# Sheet1.net
KiCad netlist of a schematic drawn in Altium Designer
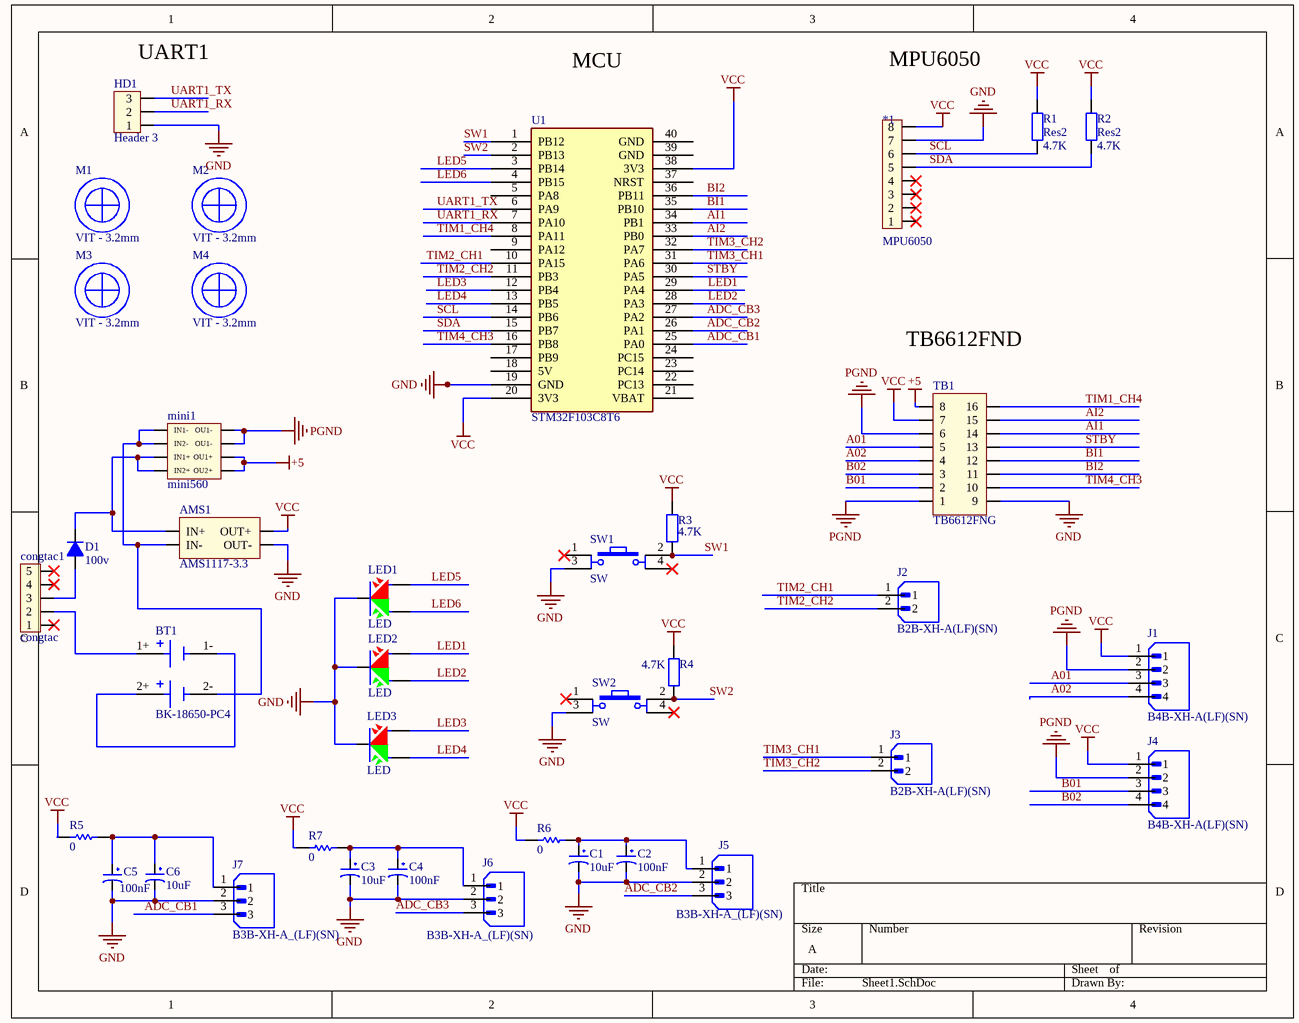
[diagram p0: Sheet1.SchDoc]

(export (version "E")
  (design (tool "Eeschema 10.0.6"))
  (components
    (comp (ref "*1") (value "MPU6050") (footprint "MPU6050") (libsource (lib "lpson") (part "MPU6050")))
    (comp (ref "AMS1")
      (value "AMS1117-3.3")
      (footprint "ASM1117-3.3")
      (libsource (lib "lpson") (part "AMS1117-3.3"))
    )
    (comp (ref "BT1")
      (value "BK-18650-PC4")
      (footprint "BAT_BK-18650-PC4")
      (description "Battery Holder (Open) 18650 2 Cell PC Pin")
      (libsource (lib "BK-18650-PC4") (part "BK-18650-PC4"))
    )
    (comp (ref "C1")
      (value "10uF")
      (footprint "CP1/2")
      (description "Cap P  0,1uF < 22uF , 16 - 50V")
      (libsource (lib "lpson") (part "CP1"))
    )
    (comp (ref "C2")
      (value "100nF")
      (footprint "CP1/2")
      (description "Cap P  0,1uF < 22uF , 16 - 50V")
      (libsource (lib "lpson") (part "CP1"))
    )
    (comp (ref "C3")
      (value "10uF")
      (footprint "CP1/2")
      (description "Cap P  0,1uF < 22uF , 16 - 50V")
      (libsource (lib "lpson") (part "CP1"))
    )
    (comp (ref "C4")
      (value "100nF")
      (footprint "CP1/2")
      (description "Cap P  0,1uF < 22uF , 16 - 50V")
      (libsource (lib "lpson") (part "CP1"))
    )
    (comp (ref "C5")
      (value "100nF")
      (footprint "CP1/2")
      (description "Cap P  0,1uF < 22uF , 16 - 50V")
      (libsource (lib "lpson") (part "CP1"))
    )
    (comp (ref "C6")
      (value "10uF")
      (footprint "CP1/2")
      (description "Cap P  0,1uF < 22uF , 16 - 50V")
      (libsource (lib "lpson") (part "CP1"))
    )
    (comp (ref "congtac1") (value "congtac") (footprint "congtac") (libsource (lib "lpson") (part "congtac")))
    (comp (ref "D1")
      (value "100v")
      (footprint "Diode 1N4007")
      (description "Cắm")
      (libsource (lib "THU VIEN SCH") (part "Diode 1N4148"))
    )
    (comp (ref "HD1") (value "Header 3") (footprint "Header_3") (libsource (lib "lpson") (part "Header3")))
    (comp (ref "J1")
      (value "B4B-XH-A(LF)(SN)")
      (footprint "JST_B4B-XH-A(LF)(SN)")
      (description "Connector Header Through Hole 4 position 0.098 (2.50mm)")
      (fields (field (name "MF") "JST Sales"))
      (libsource (lib "B4B-XH-A_LF__SN_") (part "B4B-XH-A(LF)(SN)"))
    )
    (comp (ref "J2")
      (value "B2B-XH-A(LF)(SN)")
      (footprint "JST_B2B-XH-A(LF)(SN)")
      (description "Connector Header Through Hole 2 position 0.098 (2.50mm)")
      (fields (field (name "MF") "JST Sales America Inc."))
      (libsource (lib "B2B-XH-A_LF__SN_") (part "B2B-XH-A(LF)(SN)"))
    )
    (comp (ref "J3")
      (value "B2B-XH-A(LF)(SN)")
      (footprint "JST_B2B-XH-A(LF)(SN)")
      (description "Connector Header Through Hole 2 position 0.098 (2.50mm)")
      (fields (field (name "MF") "JST Sales America Inc."))
      (libsource (lib "B2B-XH-A_LF__SN_") (part "B2B-XH-A(LF)(SN)"))
    )
    (comp (ref "J4")
      (value "B4B-XH-A(LF)(SN)")
      (footprint "JST_B4B-XH-A(LF)(SN)")
      (description "Connector Header Through Hole 4 position 0.098 (2.50mm)")
      (fields (field (name "MF") "JST Sales"))
      (libsource (lib "B4B-XH-A_LF__SN_") (part "B4B-XH-A(LF)(SN)"))
    )
    (comp (ref "J5")
      (value "B3B-XH-A_(LF)(SN)")
      (footprint "JST_B3B-XH-A (LF)(SN)")
      (description "Connector Header Through Hole 3 position 0.098 (2.50mm)")
      (fields (field (name "MF") "JST Sales America Inc.") (field (name "MP") "B3B-XH-A (LF)(SN)"))
      (libsource (lib "B3B-XH-A__LF__SN_") (part "B3B-XH-A_(LF)(SN)"))
    )
    (comp (ref "J6")
      (value "B3B-XH-A_(LF)(SN)")
      (footprint "JST_B3B-XH-A (LF)(SN)")
      (description "Connector Header Through Hole 3 position 0.098 (2.50mm)")
      (fields (field (name "MF") "JST Sales America Inc.") (field (name "MP") "B3B-XH-A (LF)(SN)"))
      (libsource (lib "B3B-XH-A__LF__SN_") (part "B3B-XH-A_(LF)(SN)"))
    )
    (comp (ref "J7")
      (value "B3B-XH-A_(LF)(SN)")
      (footprint "JST_B3B-XH-A (LF)(SN)")
      (description "Connector Header Through Hole 3 position 0.098 (2.50mm)")
      (fields (field (name "MF") "JST Sales America Inc.") (field (name "MP") "B3B-XH-A (LF)(SN)"))
      (libsource (lib "B3B-XH-A__LF__SN_") (part "B3B-XH-A_(LF)(SN)"))
    )
    (comp (ref "LED1")
      (value "LED")
      (footprint "LED-52")
      (description "LED 2 colour Green and Red")
      (libsource (lib "lpson") (part "LED2"))
    )
    (comp (ref "LED2")
      (value "LED")
      (footprint "LED-52")
      (description "LED 2 colour Green and Red")
      (libsource (lib "lpson") (part "LED2"))
    )
    (comp (ref "LED3")
      (value "LED")
      (footprint "LED-52")
      (description "LED 2 colour Green and Red")
      (libsource (lib "lpson") (part "LED2"))
    )
    (comp (ref "M1")
      (value "VIT - 3.2mm")
      (footprint "VIT - 3.2mm")
      (libsource (lib "PCCC V1.1.0_002") (part "VIT - 3.2mm"))
    )
    (comp (ref "M2")
      (value "VIT - 3.2mm")
      (footprint "VIT - 3.2mm")
      (libsource (lib "PCCC V1.1.0_002") (part "VIT - 3.2mm"))
    )
    (comp (ref "M3")
      (value "VIT - 3.2mm")
      (footprint "VIT - 3.2mm")
      (libsource (lib "PCCC V1.1.0_002") (part "VIT - 3.2mm"))
    )
    (comp (ref "M4")
      (value "VIT - 3.2mm")
      (footprint "VIT - 3.2mm")
      (libsource (lib "PCCC V1.1.0_002") (part "VIT - 3.2mm"))
    )
    (comp (ref "mini1") (value "mini560") (footprint "mini540") (libsource (lib "lpson") (part "mini560")))
    (comp (ref "R1")
      (value "Res2")
      (footprint "RES 1/4W CFR25")
      (description "Resistor")
      (fields (field (name "ALTIUM_VALUE") "4.7K") (field (name "PUBLISHER") "Altium Limited"))
      (libsource (lib "lpson") (part "Res2"))
    )
    (comp (ref "R2")
      (value "Res2")
      (footprint "RES 1/4W CFR25")
      (description "Resistor")
      (fields (field (name "ALTIUM_VALUE") "4.7K") (field (name "PUBLISHER") "Altium Limited"))
      (libsource (lib "lpson") (part "Res2"))
    )
    (comp (ref "R3")
      (value "4.7K")
      (footprint "RES 1/4W CFR25")
      (description "Resistor")
      (fields (field (name "Comment") "Res2") (field (name "PUBLISHER") "Altium Limited"))
      (libsource (lib "lpson") (part "Res2"))
    )
    (comp (ref "R4")
      (value "4.7K")
      (footprint "RES 1/4W CFR25")
      (description "Resistor")
      (fields (field (name "Comment") "Res2") (field (name "PUBLISHER") "Altium Limited"))
      (libsource (lib "lpson") (part "Res2"))
    )
    (comp (ref "R5")
      (value "0")
      (footprint "Res 1206 SMD")
      (description "RES SMD 5.1 OHM 1% 1/4W 1206")
      (fields
        (field (name "MANUFACTURER") "Yageo")
        (field (name "MANUFACTURER PART NUMBER") "RC1206FR-075R1L")
      )
      (libsource (lib "lpson") (part "RES-1206"))
    )
    (comp (ref "R6")
      (value "0")
      (footprint "Res 1206 SMD")
      (description "RES SMD 5.1 OHM 1% 1/4W 1206")
      (fields
        (field (name "MANUFACTURER") "Yageo")
        (field (name "MANUFACTURER PART NUMBER") "RC1206FR-075R1L")
      )
      (libsource (lib "lpson") (part "RES-1206"))
    )
    (comp (ref "R7")
      (value "0")
      (footprint "Res 1206 SMD")
      (description "RES SMD 5.1 OHM 1% 1/4W 1206")
      (fields
        (field (name "MANUFACTURER") "Yageo")
        (field (name "MANUFACTURER PART NUMBER") "RC1206FR-075R1L")
      )
      (libsource (lib "lpson") (part "RES-1206"))
    )
    (comp (ref "SW1")
      (value "SW")
      (footprint "SW4")
      (description "Switch button 4 pin")
      (libsource (lib "lpson") (part "SW4"))
    )
    (comp (ref "SW2")
      (value "SW")
      (footprint "SW4")
      (description "Switch button 4 pin")
      (libsource (lib "lpson") (part "SW4"))
    )
    (comp (ref "TB1")
      (value "TB6612FNG")
      (footprint "TB6612PNG")
      (libsource (lib "lpson") (part "TB6612FNG"))
    )
    (comp (ref "U1")
      (value "STM32F103C8T6")
      (footprint "Stm32 BluePill")
      (description "Designed By @Alixahedi")
      (libsource (lib "Stm32 Blue Pill") (part "BluePill"))
    )
  )
  (nets
    (net (code "1") (name "+5") (class "Default")
      (node (ref "TB1") (pin "8") (pinfunction "8_8") (pintype "passive"))
      (node (ref "mini1") (pin "7") (pinfunction "OU1+_7") (pintype "passive"))
      (node (ref "mini1") (pin "8") (pinfunction "OU2+_8") (pintype "passive"))
    )
    (net (code "2") (name "/A01") (class "Default")
      (node (ref "J1") (pin "3") (pinfunction "3_3") (pintype "passive"))
      (node (ref "TB1") (pin "5") (pinfunction "5_5") (pintype "passive"))
    )
    (net (code "3") (name "/A02") (class "Default")
      (node (ref "J1") (pin "4") (pinfunction "4_4") (pintype "passive"))
      (node (ref "TB1") (pin "4") (pinfunction "4_4") (pintype "passive"))
    )
    (net (code "4") (name "/ADC_CB1") (class "Default")
      (node (ref "J7") (pin "3") (pinfunction "3_3") (pintype "passive"))
      (node (ref "U1") (pin "25") (pinfunction "PA0_25") (pintype "passive"))
    )
    (net (code "5") (name "/ADC_CB2") (class "Default")
      (node (ref "J5") (pin "3") (pinfunction "3_3") (pintype "passive"))
      (node (ref "U1") (pin "26") (pinfunction "PA1_26") (pintype "passive"))
    )
    (net (code "6") (name "/ADC_CB3") (class "Default")
      (node (ref "J6") (pin "3") (pinfunction "3_3") (pintype "passive"))
      (node (ref "U1") (pin "27") (pinfunction "PA2_27") (pintype "passive"))
    )
    (net (code "7") (name "/AI1") (class "Default")
      (node (ref "TB1") (pin "14") (pinfunction "14_14") (pintype "passive"))
      (node (ref "U1") (pin "34") (pinfunction "PB1_34") (pintype "passive"))
    )
    (net (code "8") (name "/AI2") (class "Default")
      (node (ref "TB1") (pin "15") (pinfunction "15_15") (pintype "passive"))
      (node (ref "U1") (pin "33") (pinfunction "PB0_33") (pintype "passive"))
    )
    (net (code "9") (name "/B01") (class "Default")
      (node (ref "J4") (pin "3") (pinfunction "3_3") (pintype "passive"))
      (node (ref "TB1") (pin "2") (pinfunction "2_2") (pintype "passive"))
    )
    (net (code "10") (name "/B02") (class "Default")
      (node (ref "J4") (pin "4") (pinfunction "4_4") (pintype "passive"))
      (node (ref "TB1") (pin "3") (pinfunction "3_3") (pintype "passive"))
    )
    (net (code "11") (name "/BI1") (class "Default")
      (node (ref "TB1") (pin "12") (pinfunction "12_12") (pintype "passive"))
      (node (ref "U1") (pin "35") (pinfunction "PB10_35") (pintype "passive"))
    )
    (net (code "12") (name "/BI2") (class "Default")
      (node (ref "TB1") (pin "11") (pinfunction "11_11") (pintype "passive"))
      (node (ref "U1") (pin "36") (pinfunction "PB11_36") (pintype "passive"))
    )
    (net (code "13") (name "/LED1") (class "Default")
      (node (ref "LED2") (pin "1") (pinfunction "1_1") (pintype "passive"))
      (node (ref "U1") (pin "29") (pinfunction "PA4_29") (pintype "passive"))
    )
    (net (code "14") (name "/LED2") (class "Default")
      (node (ref "LED2") (pin "3") (pinfunction "3_3") (pintype "passive"))
      (node (ref "U1") (pin "28") (pinfunction "PA3_28") (pintype "passive"))
    )
    (net (code "15") (name "/LED3") (class "Default")
      (node (ref "LED3") (pin "1") (pinfunction "1_1") (pintype "passive"))
      (node (ref "U1") (pin "12") (pinfunction "PB4_12") (pintype "passive"))
    )
    (net (code "16") (name "/LED4") (class "Default")
      (node (ref "LED3") (pin "3") (pinfunction "3_3") (pintype "passive"))
      (node (ref "U1") (pin "13") (pinfunction "PB5_13") (pintype "passive"))
    )
    (net (code "17") (name "/LED5") (class "Default")
      (node (ref "LED1") (pin "1") (pinfunction "1_1") (pintype "passive"))
      (node (ref "U1") (pin "3") (pinfunction "PB14_3") (pintype "passive"))
    )
    (net (code "18") (name "/LED6") (class "Default")
      (node (ref "LED1") (pin "3") (pinfunction "3_3") (pintype "passive"))
      (node (ref "U1") (pin "4") (pinfunction "PB15_4") (pintype "passive"))
    )
    (net (code "19") (name "/SCL") (class "Default")
      (node (ref "*1") (pin "6") (pinfunction "6_6") (pintype "passive"))
      (node (ref "R1") (pin "1") (pinfunction "1_1") (pintype "passive"))
      (node (ref "U1") (pin "14") (pinfunction "PB6_14") (pintype "passive"))
    )
    (net (code "20") (name "/SDA") (class "Default")
      (node (ref "*1") (pin "5") (pinfunction "5_5") (pintype "passive"))
      (node (ref "R2") (pin "1") (pinfunction "1_1") (pintype "passive"))
      (node (ref "U1") (pin "15") (pinfunction "PB7_15") (pintype "passive"))
    )
    (net (code "21") (name "/STBY") (class "Default")
      (node (ref "TB1") (pin "13") (pinfunction "13_13") (pintype "passive"))
      (node (ref "U1") (pin "30") (pinfunction "PA5_30") (pintype "passive"))
    )
    (net (code "22") (name "/SW1") (class "Default")
      (node (ref "R3") (pin "1") (pinfunction "1_1") (pintype "passive"))
      (node (ref "SW1") (pin "2") (pintype "passive"))
      (node (ref "U1") (pin "1") (pinfunction "PB12_1") (pintype "passive"))
    )
    (net (code "23") (name "/SW2") (class "Default")
      (node (ref "R4") (pin "1") (pinfunction "1_1") (pintype "passive"))
      (node (ref "SW2") (pin "2") (pintype "passive"))
      (node (ref "U1") (pin "2") (pinfunction "PB13_2") (pintype "passive"))
    )
    (net (code "24") (name "/TIM1_CH4") (class "Default")
      (node (ref "TB1") (pin "16") (pinfunction "16_16") (pintype "passive"))
      (node (ref "U1") (pin "8") (pinfunction "PA11_8") (pintype "passive"))
    )
    (net (code "25") (name "/TIM2_CH1") (class "Default")
      (node (ref "J2") (pin "1") (pinfunction "1_1") (pintype "passive"))
      (node (ref "U1") (pin "10") (pinfunction "PA15_10") (pintype "passive"))
    )
    (net (code "26") (name "/TIM2_CH2") (class "Default")
      (node (ref "J2") (pin "2") (pinfunction "2_2") (pintype "passive"))
      (node (ref "U1") (pin "11") (pinfunction "PB3_11") (pintype "passive"))
    )
    (net (code "27") (name "/TIM3_CH1") (class "Default")
      (node (ref "J3") (pin "1") (pinfunction "1_1") (pintype "passive"))
      (node (ref "U1") (pin "31") (pinfunction "PA6_31") (pintype "passive"))
    )
    (net (code "28") (name "/TIM3_CH2") (class "Default")
      (node (ref "J3") (pin "2") (pinfunction "2_2") (pintype "passive"))
      (node (ref "U1") (pin "32") (pinfunction "PA7_32") (pintype "passive"))
    )
    (net (code "29") (name "/TIM4_CH3") (class "Default")
      (node (ref "TB1") (pin "10") (pinfunction "10_10") (pintype "passive"))
      (node (ref "U1") (pin "16") (pinfunction "PB8_16") (pintype "passive"))
    )
    (net (code "30") (name "/UART1_RX") (class "Default")
      (node (ref "HD1") (pin "2") (pinfunction "2_2") (pintype "passive"))
      (node (ref "U1") (pin "7") (pinfunction "PA10_7") (pintype "passive"))
    )
    (net (code "31") (name "/UART1_TX") (class "Default")
      (node (ref "HD1") (pin "3") (pinfunction "3_3") (pintype "passive"))
      (node (ref "U1") (pin "6") (pinfunction "PA9_6") (pintype "passive"))
    )
    (net (code "32") (name "GND") (class "Default")
      (node (ref "*1") (pin "7") (pinfunction "7_7") (pintype "passive"))
      (node (ref "AMS1") (pin "4") (pinfunction "OUT-_4") (pintype "passive"))
      (node (ref "C1") (pin "2") (pinfunction "2_2") (pintype "passive"))
      (node (ref "C2") (pin "2") (pinfunction "2_2") (pintype "passive"))
      (node (ref "C3") (pin "2") (pinfunction "2_2") (pintype "passive"))
      (node (ref "C4") (pin "2") (pinfunction "2_2") (pintype "passive"))
      (node (ref "C5") (pin "2") (pinfunction "2_2") (pintype "passive"))
      (node (ref "C6") (pin "2") (pinfunction "2_2") (pintype "passive"))
      (node (ref "HD1") (pin "1") (pinfunction "1_1") (pintype "passive"))
      (node (ref "J5") (pin "2") (pinfunction "2_2") (pintype "passive"))
      (node (ref "J6") (pin "2") (pinfunction "2_2") (pintype "passive"))
      (node (ref "J7") (pin "2") (pinfunction "2_2") (pintype "passive"))
      (node (ref "LED1") (pin "2") (pinfunction "2_2") (pintype "passive"))
      (node (ref "LED2") (pin "2") (pinfunction "2_2") (pintype "passive"))
      (node (ref "LED3") (pin "2") (pinfunction "2_2") (pintype "passive"))
      (node (ref "SW1") (pin "3") (pintype "passive"))
      (node (ref "SW2") (pin "3") (pintype "passive"))
      (node (ref "TB1") (pin "9") (pinfunction "9_9") (pintype "passive"))
      (node (ref "U1") (pin "19") (pinfunction "GND_19") (pintype "passive"))
    )
    (net (code "33") (name "Net-(AMS1-IN+)") (class "Default")
      (node (ref "AMS1") (pin "1") (pinfunction "IN+_1") (pintype "passive"))
      (node (ref "D1") (pin "2") (pinfunction "K_2") (pintype "passive"))
      (node (ref "mini1") (pin "3") (pinfunction "IN1+_3") (pintype "passive"))
      (node (ref "mini1") (pin "4") (pinfunction "IN2+_4") (pintype "passive"))
    )
    (net (code "34") (name "Net-(AMS1-IN-)") (class "Default")
      (node (ref "AMS1") (pin "2") (pinfunction "IN-_2") (pintype "passive"))
      (node (ref "BT1") (pin "2-") (pinfunction "2-_2-") (pintype "passive"))
      (node (ref "mini1") (pin "1") (pinfunction "IN1-_1") (pintype "passive"))
      (node (ref "mini1") (pin "2") (pinfunction "IN2-_2") (pintype "passive"))
    )
    (net (code "35") (name "Net-(BT1-Pad1+)") (class "Default")
      (node (ref "BT1") (pin "1+") (pinfunction "1+_1+") (pintype "passive"))
      (node (ref "congtac1") (pin "2") (pinfunction "2_2") (pintype "passive"))
    )
    (net (code "36") (name "Net-(BT1-Pad1-)") (class "Default")
      (node (ref "BT1") (pin "1-") (pinfunction "1-_1-") (pintype "passive"))
      (node (ref "BT1") (pin "2+") (pinfunction "2+_2+") (pintype "passive"))
    )
    (net (code "37") (name "Net-(C1-Pad1)") (class "Default")
      (node (ref "C1") (pin "1") (pinfunction "1_1") (pintype "passive"))
      (node (ref "C2") (pin "1") (pinfunction "1_1") (pintype "passive"))
      (node (ref "J5") (pin "1") (pinfunction "1_1") (pintype "passive"))
      (node (ref "R6") (pin "1") (pinfunction "1_1") (pintype "passive"))
    )
    (net (code "38") (name "Net-(C3-Pad1)") (class "Default")
      (node (ref "C3") (pin "1") (pinfunction "1_1") (pintype "passive"))
      (node (ref "C4") (pin "1") (pinfunction "1_1") (pintype "passive"))
      (node (ref "J6") (pin "1") (pinfunction "1_1") (pintype "passive"))
      (node (ref "R7") (pin "1") (pinfunction "1_1") (pintype "passive"))
    )
    (net (code "39") (name "Net-(C5-Pad1)") (class "Default")
      (node (ref "C5") (pin "1") (pinfunction "1_1") (pintype "passive"))
      (node (ref "C6") (pin "1") (pinfunction "1_1") (pintype "passive"))
      (node (ref "J7") (pin "1") (pinfunction "1_1") (pintype "passive"))
      (node (ref "R5") (pin "1") (pinfunction "1_1") (pintype "passive"))
    )
    (net (code "40") (name "Net-(D1-A)") (class "Default")
      (node (ref "D1") (pin "1") (pinfunction "A_1") (pintype "passive"))
      (node (ref "congtac1") (pin "3") (pinfunction "3_3") (pintype "passive"))
    )
    (net (code "41") (name "PGND") (class "Default")
      (node (ref "J1") (pin "2") (pinfunction "2_2") (pintype "passive"))
      (node (ref "J4") (pin "2") (pinfunction "2_2") (pintype "passive"))
      (node (ref "TB1") (pin "1") (pinfunction "1_1") (pintype "passive"))
      (node (ref "TB1") (pin "6") (pinfunction "6_6") (pintype "passive"))
      (node (ref "mini1") (pin "5") (pinfunction "OU1-_5") (pintype "passive"))
      (node (ref "mini1") (pin "6") (pinfunction "OU1-_6") (pintype "passive"))
    )
    (net (code "42") (name "VCC") (class "Default")
      (node (ref "*1") (pin "8") (pinfunction "8_8") (pintype "passive"))
      (node (ref "AMS1") (pin "3") (pinfunction "OUT+_3") (pintype "passive"))
      (node (ref "J1") (pin "1") (pinfunction "1_1") (pintype "passive"))
      (node (ref "J4") (pin "1") (pinfunction "1_1") (pintype "passive"))
      (node (ref "R1") (pin "2") (pinfunction "2_2") (pintype "passive"))
      (node (ref "R2") (pin "2") (pinfunction "2_2") (pintype "passive"))
      (node (ref "R3") (pin "2") (pinfunction "2_2") (pintype "passive"))
      (node (ref "R4") (pin "2") (pinfunction "2_2") (pintype "passive"))
      (node (ref "R5") (pin "2") (pinfunction "2_2") (pintype "passive"))
      (node (ref "R6") (pin "2") (pinfunction "2_2") (pintype "passive"))
      (node (ref "R7") (pin "2") (pinfunction "2_2") (pintype "passive"))
      (node (ref "TB1") (pin "7") (pinfunction "7_7") (pintype "passive"))
      (node (ref "U1") (pin "20") (pinfunction "3V3_20") (pintype "passive"))
      (node (ref "U1") (pin "38") (pinfunction "3V3_38") (pintype "passive"))
    )
    (net (code "43") (name "unconnected-(*1-Pad1)") (class "Default")
      (node (ref "*1") (pin "1") (pinfunction "1_1") (pintype "passive+no_connect"))
    )
    (net (code "44") (name "unconnected-(*1-Pad2)") (class "Default")
      (node (ref "*1") (pin "2") (pinfunction "2_2") (pintype "passive+no_connect"))
    )
    (net (code "45") (name "unconnected-(*1-Pad3)") (class "Default")
      (node (ref "*1") (pin "3") (pinfunction "3_3") (pintype "passive+no_connect"))
    )
    (net (code "46") (name "unconnected-(*1-Pad4)") (class "Default")
      (node (ref "*1") (pin "4") (pinfunction "4_4") (pintype "passive+no_connect"))
    )
    (net (code "47") (name "unconnected-(SW1-Pad1)") (class "Default")
      (node (ref "SW1") (pin "1") (pintype "passive+no_connect"))
    )
    (net (code "48") (name "unconnected-(SW1-Pad4)") (class "Default")
      (node (ref "SW1") (pin "4") (pintype "passive+no_connect"))
    )
    (net (code "49") (name "unconnected-(SW2-Pad1)") (class "Default")
      (node (ref "SW2") (pin "1") (pintype "passive+no_connect"))
    )
    (net (code "50") (name "unconnected-(SW2-Pad4)") (class "Default")
      (node (ref "SW2") (pin "4") (pintype "passive+no_connect"))
    )
    (net (code "51") (name "unconnected-(U1-5V-Pad18)") (class "Default")
      (node (ref "U1") (pin "18") (pinfunction "5V_18") (pintype "passive"))
    )
    (net (code "52") (name "unconnected-(U1-GND-Pad39)") (class "Default")
      (node (ref "U1") (pin "39") (pinfunction "GND_39") (pintype "passive"))
    )
    (net (code "53") (name "unconnected-(U1-GND-Pad40)") (class "Default")
      (node (ref "U1") (pin "40") (pinfunction "GND_40") (pintype "passive"))
    )
    (net (code "54") (name "unconnected-(U1-NRST-Pad37)") (class "Default")
      (node (ref "U1") (pin "37") (pinfunction "NRST_37") (pintype "passive"))
    )
    (net (code "55") (name "unconnected-(U1-PA8-Pad5)") (class "Default")
      (node (ref "U1") (pin "5") (pinfunction "PA8_5") (pintype "passive"))
    )
    (net (code "56") (name "unconnected-(U1-PA12-Pad9)") (class "Default")
      (node (ref "U1") (pin "9") (pinfunction "PA12_9") (pintype "passive"))
    )
    (net (code "57") (name "unconnected-(U1-PB9-Pad17)") (class "Default")
      (node (ref "U1") (pin "17") (pinfunction "PB9_17") (pintype "passive"))
    )
    (net (code "58") (name "unconnected-(U1-PC13-Pad22)") (class "Default")
      (node (ref "U1") (pin "22") (pinfunction "PC13_22") (pintype "passive"))
    )
    (net (code "59") (name "unconnected-(U1-PC14-Pad23)") (class "Default")
      (node (ref "U1") (pin "23") (pinfunction "PC14_23") (pintype "passive"))
    )
    (net (code "60") (name "unconnected-(U1-PC15-Pad24)") (class "Default")
      (node (ref "U1") (pin "24") (pinfunction "PC15_24") (pintype "passive"))
    )
    (net (code "61") (name "unconnected-(U1-VBAT-Pad21)") (class "Default")
      (node (ref "U1") (pin "21") (pinfunction "VBAT_21") (pintype "passive"))
    )
    (net (code "62") (name "unconnected-(congtac1-Pad1)") (class "Default")
      (node (ref "congtac1") (pin "1") (pinfunction "1_1") (pintype "passive+no_connect"))
    )
    (net (code "63") (name "unconnected-(congtac1-Pad4)") (class "Default")
      (node (ref "congtac1") (pin "4") (pinfunction "4_4") (pintype "passive+no_connect"))
    )
    (net (code "64") (name "unconnected-(congtac1-Pad5)") (class "Default")
      (node (ref "congtac1") (pin "5") (pinfunction "5_5") (pintype "passive+no_connect"))
    )
  )
)
